# SolarSimulatorPanel.net
KiCad netlist of a schematic drawn in EAGLE
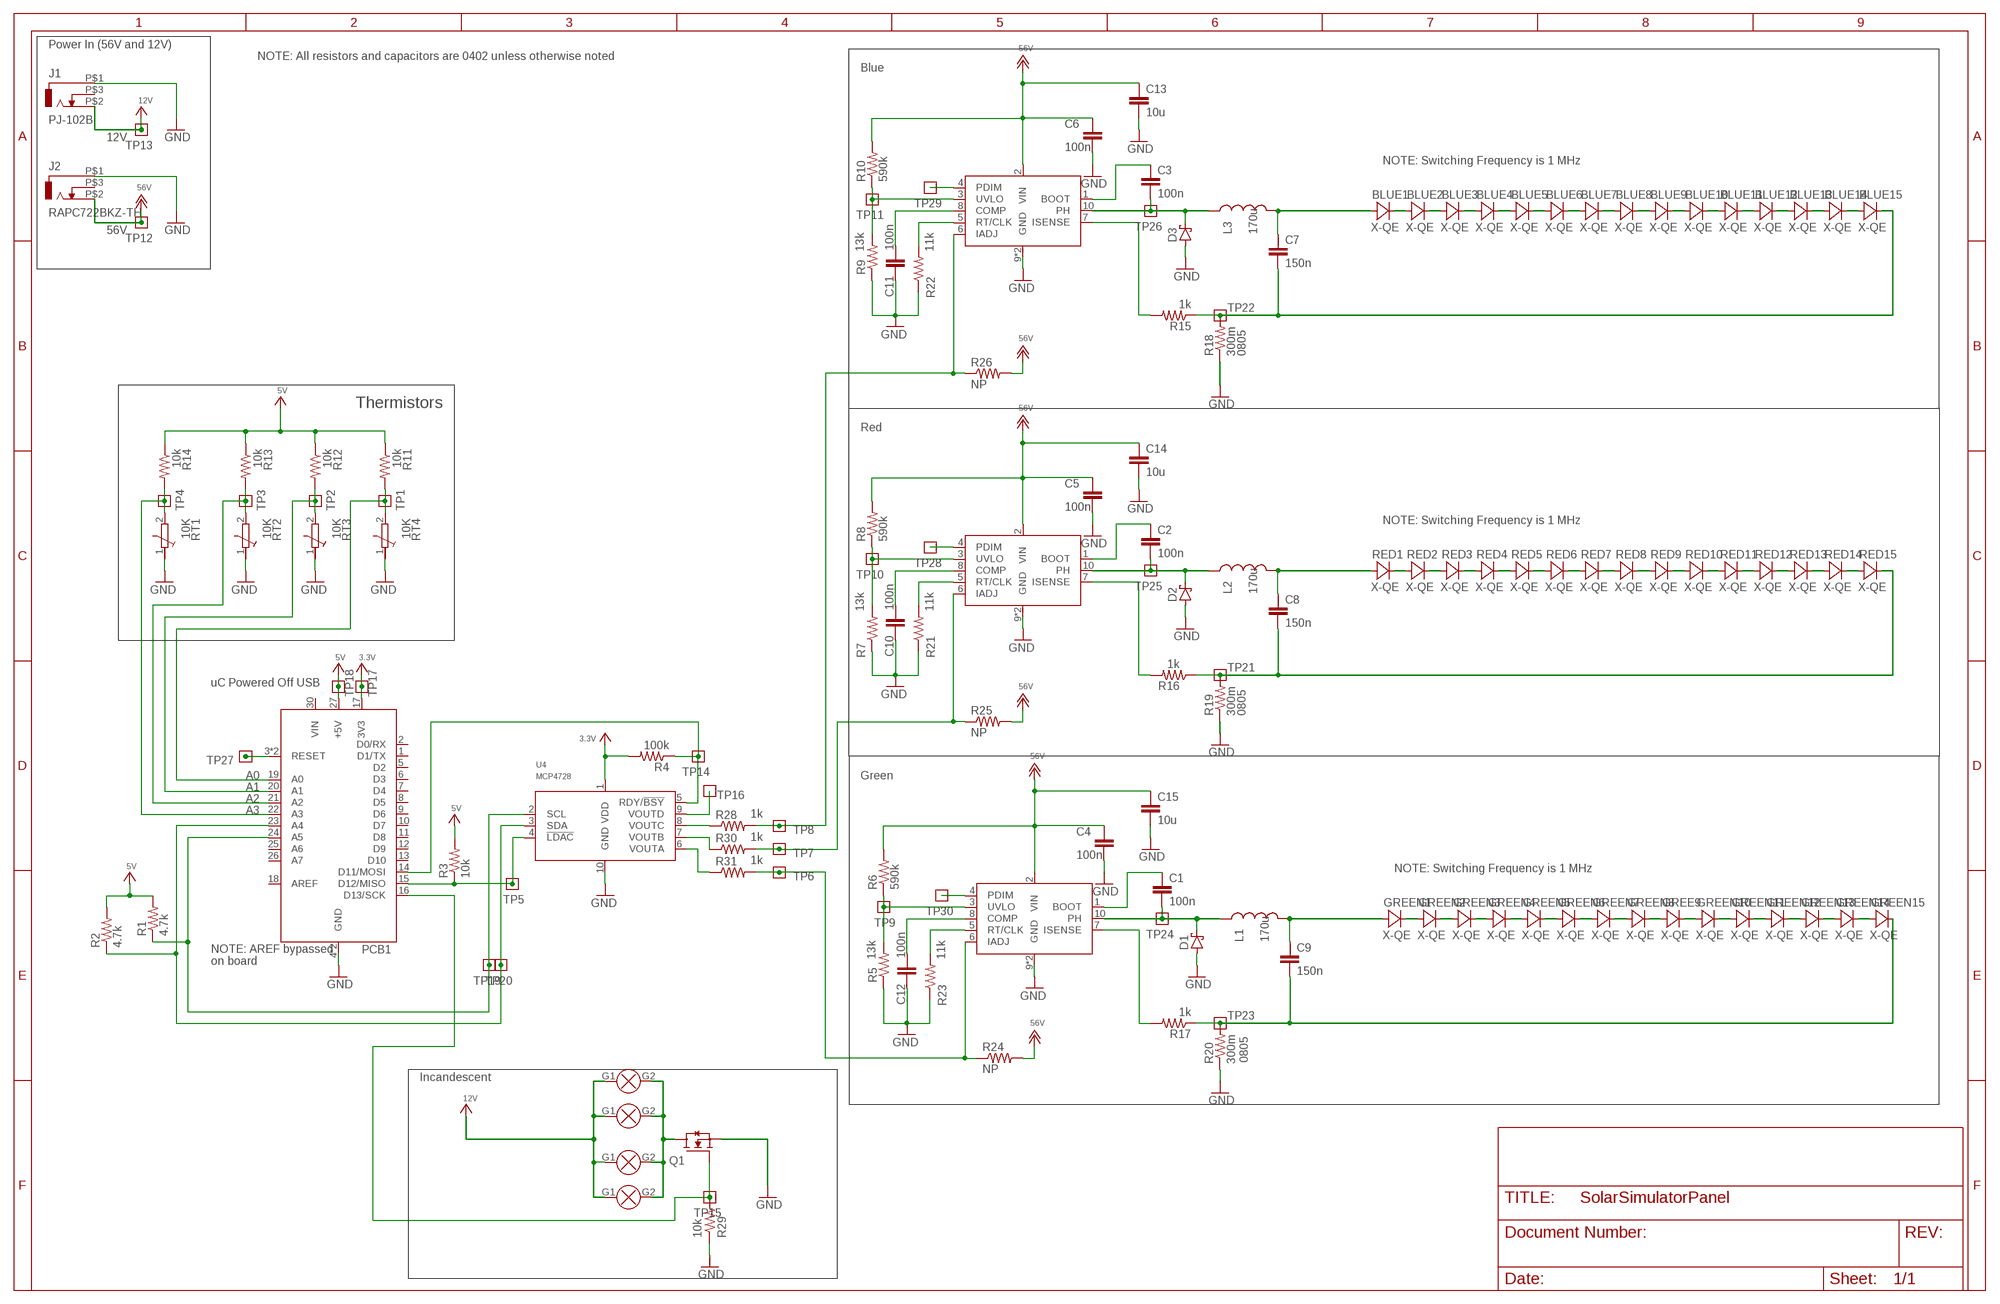
[diagram p0: schematic, sheet 1]

(export (version "E")
  (design (tool "Eeschema 10.0.6"))
  (components
    (comp (ref "BLUE1")
      (value "X-QE")
      (footprint "eagle-import:X-QE")
      (fields (field (name "MFR") "Cree") (field (name "MPN") "XQEROY-00-0000-000000L01"))
      (libsource (lib "eagle-import") (part "X-QE"))
    )
    (comp (ref "BLUE2")
      (value "X-QE")
      (footprint "eagle-import:X-QE")
      (fields (field (name "MFR") "Cree") (field (name "MPN") "XQEROY-00-0000-000000L01"))
      (libsource (lib "eagle-import") (part "X-QE"))
    )
    (comp (ref "BLUE3")
      (value "X-QE")
      (footprint "eagle-import:X-QE")
      (fields (field (name "MFR") "Cree") (field (name "MPN") "XQEROY-00-0000-000000L01"))
      (libsource (lib "eagle-import") (part "X-QE"))
    )
    (comp (ref "BLUE4")
      (value "X-QE")
      (footprint "eagle-import:X-QE")
      (fields (field (name "MFR") "Cree") (field (name "MPN") "XQEROY-00-0000-000000L01"))
      (libsource (lib "eagle-import") (part "X-QE"))
    )
    (comp (ref "BLUE5")
      (value "X-QE")
      (footprint "eagle-import:X-QE")
      (fields (field (name "MFR") "Cree") (field (name "MPN") "XQEROY-00-0000-000000L01"))
      (libsource (lib "eagle-import") (part "X-QE"))
    )
    (comp (ref "BLUE6")
      (value "X-QE")
      (footprint "eagle-import:X-QE")
      (fields (field (name "MFR") "Cree") (field (name "MPN") "XQEROY-00-0000-000000L01"))
      (libsource (lib "eagle-import") (part "X-QE"))
    )
    (comp (ref "BLUE7")
      (value "X-QE")
      (footprint "eagle-import:X-QE")
      (fields (field (name "MFR") "Cree") (field (name "MPN") "XQEROY-00-0000-000000L01"))
      (libsource (lib "eagle-import") (part "X-QE"))
    )
    (comp (ref "BLUE8")
      (value "X-QE")
      (footprint "eagle-import:X-QE")
      (fields (field (name "MFR") "Cree") (field (name "MPN") "XQEROY-00-0000-000000L01"))
      (libsource (lib "eagle-import") (part "X-QE"))
    )
    (comp (ref "BLUE9")
      (value "X-QE")
      (footprint "eagle-import:X-QE")
      (fields (field (name "MFR") "Cree") (field (name "MPN") "XQEROY-00-0000-000000L01"))
      (libsource (lib "eagle-import") (part "X-QE"))
    )
    (comp (ref "BLUE10")
      (value "X-QE")
      (footprint "eagle-import:X-QE")
      (fields (field (name "MFR") "Cree") (field (name "MPN") "XQEROY-00-0000-000000L01"))
      (libsource (lib "eagle-import") (part "X-QE"))
    )
    (comp (ref "BLUE11")
      (value "X-QE")
      (footprint "eagle-import:X-QE")
      (fields (field (name "MFR") "Cree") (field (name "MPN") "XQEROY-00-0000-000000L01"))
      (libsource (lib "eagle-import") (part "X-QE"))
    )
    (comp (ref "BLUE12")
      (value "X-QE")
      (footprint "eagle-import:X-QE")
      (fields (field (name "MFR") "Cree") (field (name "MPN") "XQEROY-00-0000-000000L01"))
      (libsource (lib "eagle-import") (part "X-QE"))
    )
    (comp (ref "BLUE13")
      (value "X-QE")
      (footprint "eagle-import:X-QE")
      (fields (field (name "MFR") "Cree") (field (name "MPN") "XQEROY-00-0000-000000L01"))
      (libsource (lib "eagle-import") (part "X-QE"))
    )
    (comp (ref "BLUE14")
      (value "X-QE")
      (footprint "eagle-import:X-QE")
      (fields (field (name "MFR") "Cree") (field (name "MPN") "XQEROY-00-0000-000000L01"))
      (libsource (lib "eagle-import") (part "X-QE"))
    )
    (comp (ref "BLUE15")
      (value "X-QE")
      (footprint "eagle-import:X-QE")
      (fields (field (name "MFR") "Cree") (field (name "MPN") "XQEROY-00-0000-000000L01"))
      (libsource (lib "eagle-import") (part "X-QE"))
    )
    (comp (ref "C1")
      (value "100n")
      (footprint "eagle-import:.0402-A-NOSILK")
      (fields (field (name "MFR") "Murata") (field (name "MPN") "GRM155R62A104KE14D"))
      (libsource (lib "eagle-import") (part "C-EU0402-A-NOSILK"))
    )
    (comp (ref "C2")
      (value "100n")
      (footprint "eagle-import:.0402-A-NOSILK")
      (fields (field (name "MFR") "Murata") (field (name "MPN") "GRM155R62A104KE14D"))
      (libsource (lib "eagle-import") (part "C-EU0402-A-NOSILK"))
    )
    (comp (ref "C3")
      (value "100n")
      (footprint "eagle-import:.0402-A-NOSILK")
      (libsource (lib "eagle-import") (part "C-EU0402-A-NOSILK"))
    )
    (comp (ref "C4")
      (value "100n")
      (footprint "eagle-import:.0402-A-NOSILK")
      (fields (field (name "MFR") "Murata") (field (name "MPN") "GRM155R62A104KE14D"))
      (libsource (lib "eagle-import") (part "C-EU0402-A-NOSILK"))
    )
    (comp (ref "C5")
      (value "100n")
      (footprint "eagle-import:.0402-A-NOSILK")
      (fields (field (name "MFR") "Murata") (field (name "MPN") "GRM155R62A104KE14D"))
      (libsource (lib "eagle-import") (part "C-EU0402-A-NOSILK"))
    )
    (comp (ref "C6")
      (value "100n")
      (footprint "eagle-import:.0402-A-NOSILK")
      (fields (field (name "MFR") "Murata") (field (name "MPN") "GRM155R62A104KE14D"))
      (libsource (lib "eagle-import") (part "C-EU0402-A-NOSILK"))
    )
    (comp (ref "C7")
      (value "150n")
      (footprint "eagle-import:C0805K")
      (fields (field (name "MFR") "Murata") (field (name "MPN") "GRM188R71H154KAC4D"))
      (libsource (lib "eagle-import") (part "rcl_334_C-EUC0805K"))
    )
    (comp (ref "C8")
      (value "150n")
      (footprint "eagle-import:C0805K")
      (fields (field (name "MFR") "Murata") (field (name "MPN") "GRM188R71H154KAC4D"))
      (libsource (lib "eagle-import") (part "rcl_334_C-EUC0805K"))
    )
    (comp (ref "C9")
      (value "150n")
      (footprint "eagle-import:C0805K")
      (fields (field (name "MFR") "Murata") (field (name "MPN") "GRM188R71H154KAC4D"))
      (libsource (lib "eagle-import") (part "rcl_334_C-EUC0805K"))
    )
    (comp (ref "C10")
      (value "100n")
      (footprint "eagle-import:.0402-A-NOSILK")
      (fields (field (name "MFR") "Murata") (field (name "MPN") "GRM155R62A104KE14D"))
      (libsource (lib "eagle-import") (part "C-EU0402-A-NOSILK"))
    )
    (comp (ref "C11")
      (value "100n")
      (footprint "eagle-import:.0402-A-NOSILK")
      (fields (field (name "MFR") "Murata") (field (name "MPN") "GRM155R62A104KE14D"))
      (libsource (lib "eagle-import") (part "C-EU0402-A-NOSILK"))
    )
    (comp (ref "C12")
      (value "100n")
      (footprint "eagle-import:.0402-A-NOSILK")
      (fields (field (name "MFR") "Murata") (field (name "MPN") "GRM155R62A104KE14D"))
      (libsource (lib "eagle-import") (part "C-EU0402-A-NOSILK"))
    )
    (comp (ref "C13")
      (value "10u")
      (footprint "eagle-import:C2220K")
      (fields (field (name "MFR") "AVX") (field (name "MPN") "22201C106MAT2A"))
      (libsource (lib "eagle-import") (part "rcl_334_C-EUC2220K"))
    )
    (comp (ref "C14")
      (value "10u")
      (footprint "eagle-import:C2220K")
      (fields (field (name "MFR") "AVX") (field (name "MPN") "22201C106MAT2A"))
      (libsource (lib "eagle-import") (part "rcl_334_C-EUC2220K"))
    )
    (comp (ref "C15")
      (value "10u")
      (footprint "eagle-import:C2220K")
      (fields (field (name "MFR") "AVX") (field (name "MPN") "22201C106MAT2A"))
      (libsource (lib "eagle-import") (part "rcl_334_C-EUC2220K"))
    )
    (comp (ref "D1")
      (value "D-MCC-SS2150")
      (footprint "eagle-import:DO-214AC")
      (fields (field (name "MFR") "Micro") (field (name "MPN") "SS2150-LTP"))
      (libsource (lib "eagle-import") (part "D-MCC-SS2150"))
    )
    (comp (ref "D2")
      (value "D-MCC-SS2150")
      (footprint "eagle-import:DO-214AC")
      (fields (field (name "MFR") "Micro") (field (name "MPN") "SS2150-LTP"))
      (libsource (lib "eagle-import") (part "D-MCC-SS2150"))
    )
    (comp (ref "D3")
      (value "D-MCC-SS2150")
      (footprint "eagle-import:DO-214AC")
      (fields (field (name "MFR") "Micro") (field (name "MPN") "SS2150-LTP"))
      (libsource (lib "eagle-import") (part "D-MCC-SS2150"))
    )
    (comp (ref "GREE9")
      (value "X-QE")
      (footprint "eagle-import:X-QE")
      (fields (field (name "MFR") "Cree") (field (name "MPN") "XQEGRN-00-0000-000000D03"))
      (libsource (lib "eagle-import") (part "X-QE"))
    )
    (comp (ref "GREEN1")
      (value "X-QE")
      (footprint "eagle-import:X-QE")
      (fields (field (name "MFR") "Cree") (field (name "MPN") "XQEGRN-00-0000-000000D03"))
      (libsource (lib "eagle-import") (part "X-QE"))
    )
    (comp (ref "GREEN2")
      (value "X-QE")
      (footprint "eagle-import:X-QE")
      (fields (field (name "MFR") "Cree") (field (name "MPN") "XQEGRN-00-0000-000000D03"))
      (libsource (lib "eagle-import") (part "X-QE"))
    )
    (comp (ref "GREEN3")
      (value "X-QE")
      (footprint "eagle-import:X-QE")
      (fields (field (name "MFR") "Cree") (field (name "MPN") "XQEGRN-00-0000-000000D03"))
      (libsource (lib "eagle-import") (part "X-QE"))
    )
    (comp (ref "GREEN4")
      (value "X-QE")
      (footprint "eagle-import:X-QE")
      (fields (field (name "MFR") "Cree") (field (name "MPN") "XQEGRN-00-0000-000000D03"))
      (libsource (lib "eagle-import") (part "X-QE"))
    )
    (comp (ref "GREEN5")
      (value "X-QE")
      (footprint "eagle-import:X-QE")
      (fields (field (name "MFR") "Cree") (field (name "MPN") "XQEGRN-00-0000-000000D03"))
      (libsource (lib "eagle-import") (part "X-QE"))
    )
    (comp (ref "GREEN6")
      (value "X-QE")
      (footprint "eagle-import:X-QE")
      (fields (field (name "MFR") "Cree") (field (name "MPN") "XQEGRN-00-0000-000000D03"))
      (libsource (lib "eagle-import") (part "X-QE"))
    )
    (comp (ref "GREEN7")
      (value "X-QE")
      (footprint "eagle-import:X-QE")
      (fields (field (name "MFR") "Cree") (field (name "MPN") "XQEGRN-00-0000-000000D03"))
      (libsource (lib "eagle-import") (part "X-QE"))
    )
    (comp (ref "GREEN8")
      (value "X-QE")
      (footprint "eagle-import:X-QE")
      (fields (field (name "MFR") "Cree") (field (name "MPN") "XQEGRN-00-0000-000000D03"))
      (libsource (lib "eagle-import") (part "X-QE"))
    )
    (comp (ref "GREEN10")
      (value "X-QE")
      (footprint "eagle-import:X-QE")
      (fields (field (name "MFR") "Cree") (field (name "MPN") "XQEGRN-00-0000-000000D03"))
      (libsource (lib "eagle-import") (part "X-QE"))
    )
    (comp (ref "GREEN11")
      (value "X-QE")
      (footprint "eagle-import:X-QE")
      (fields (field (name "MFR") "Cree") (field (name "MPN") "XQEGRN-00-0000-000000D03"))
      (libsource (lib "eagle-import") (part "X-QE"))
    )
    (comp (ref "GREEN12")
      (value "X-QE")
      (footprint "eagle-import:X-QE")
      (fields (field (name "MFR") "Cree") (field (name "MPN") "XQEGRN-00-0000-000000D03"))
      (libsource (lib "eagle-import") (part "X-QE"))
    )
    (comp (ref "GREEN13")
      (value "X-QE")
      (footprint "eagle-import:X-QE")
      (fields (field (name "MFR") "Cree") (field (name "MPN") "XQEGRN-00-0000-000000D03"))
      (libsource (lib "eagle-import") (part "X-QE"))
    )
    (comp (ref "GREEN14")
      (value "X-QE")
      (footprint "eagle-import:X-QE")
      (fields (field (name "MFR") "Cree") (field (name "MPN") "XQEGRN-00-0000-000000D03"))
      (libsource (lib "eagle-import") (part "X-QE"))
    )
    (comp (ref "GREEN15")
      (value "X-QE")
      (footprint "eagle-import:X-QE")
      (fields (field (name "MFR") "Cree") (field (name "MPN") "XQEGRN-00-0000-000000D03"))
      (libsource (lib "eagle-import") (part "X-QE"))
    )
    (comp (ref "J1")
      (value "PJ-102B")
      (footprint "eagle-import:CUI_PJ-102B")
      (fields (field (name "MF") "CUI Devices") (field (name "MFR") "Conec"))
      (libsource (lib "eagle-import") (part "PJ-102B"))
    )
    (comp (ref "J2")
      (value "RAPC722BKZ-TH")
      (footprint "eagle-import:RAPC722BKZ")
      (fields (field (name "MFR") "SwitchCraft") (field (name "MPN") "RAPC722BKZ"))
      (libsource (lib "eagle-import") (part "RAPC722BKZ-TH"))
    )
    (comp (ref "L1")
      (value "170u")
      (footprint "eagle-import:1212NONSTANDARD")
      (fields (field (name "MFR") "Amgis") (field (name "MPN") "SH150S-1.02-168"))
      (libsource (lib "eagle-import") (part "7447709681"))
    )
    (comp (ref "L2")
      (value "170u")
      (footprint "eagle-import:1212NONSTANDARD")
      (fields (field (name "MFR") "Amgis") (field (name "MPN") "SH150S-1.02-168"))
      (libsource (lib "eagle-import") (part "7447709681"))
    )
    (comp (ref "L3")
      (value "170u")
      (footprint "eagle-import:1212NONSTANDARD")
      (fields (field (name "MFR") "Amgis") (field (name "MPN") "SH150S-1.02-168"))
      (libsource (lib "eagle-import") (part "7447709681"))
    )
    (comp (ref "PCB1")
      (value "ARDUINO_NANO")
      (footprint "eagle-import:ARDUINO_NANO_SHIELD")
      (libsource (lib "eagle-import") (part "ARDUINO_NANO"))
    )
    (comp (ref "Q1")
      (value "NCH-SOT223")
      (footprint "eagle-import:SOT223")
      (fields (field (name "MFR") "Diodes") (field (name "MPN") "DMN6068SE"))
      (libsource (lib "eagle-import") (part "NCH-SOT223"))
    )
    (comp (ref "R1")
      (value "4.7k")
      (footprint "eagle-import:.0402-A-NOSILK")
      (fields (field (name "MFR") "Yageo") (field (name "MPN") "RC0402JR-074K7L"))
      (libsource (lib "eagle-import") (part "R-US_0402-A-NOSILK"))
    )
    (comp (ref "R2")
      (value "4.7k")
      (footprint "eagle-import:.0402-A-NOSILK")
      (fields (field (name "MFR") "Yageo") (field (name "MPN") "311-4.7KJRCT-ND"))
      (libsource (lib "eagle-import") (part "R-US_0402-A-NOSILK"))
    )
    (comp (ref "R3")
      (value "10k")
      (footprint "eagle-import:.0402-A-NOSILK")
      (fields (field (name "MPN") "RC0402FR-0710KL"))
      (libsource (lib "eagle-import") (part "R-US_0402-A-NOSILK"))
    )
    (comp (ref "R4")
      (value "100k")
      (footprint "eagle-import:.0402-A-NOSILK")
      (libsource (lib "eagle-import") (part "R-US_0402-A-NOSILK"))
    )
    (comp (ref "R5")
      (value "13k")
      (footprint "eagle-import:.0402-A-NOSILK")
      (fields (field (name "MFR") "Panasonic") (field (name "MPN") "ERA-2AEB133X"))
      (libsource (lib "eagle-import") (part "R-US_0402-A-NOSILK"))
    )
    (comp (ref "R6")
      (value "590k")
      (footprint "eagle-import:.0402-A-NOSILK")
      (fields (field (name "MFR") "Stackpole") (field (name "MPN") "RMCF0402FT590K"))
      (libsource (lib "eagle-import") (part "R-US_0402-A-NOSILK"))
    )
    (comp (ref "R7")
      (value "13k")
      (footprint "eagle-import:.0402-A-NOSILK")
      (fields (field (name "MFR") "Panasonic") (field (name "MPN") "ERA-2AEB133X"))
      (libsource (lib "eagle-import") (part "R-US_0402-A-NOSILK"))
    )
    (comp (ref "R8")
      (value "590k")
      (footprint "eagle-import:.0402-A-NOSILK")
      (fields (field (name "MFR") "Stackpole") (field (name "MPN") "RMCF0402FT590K"))
      (libsource (lib "eagle-import") (part "R-US_0402-A-NOSILK"))
    )
    (comp (ref "R9")
      (value "13k")
      (footprint "eagle-import:.0402-A-NOSILK")
      (fields (field (name "MFR") "Panasonic") (field (name "MPN") "ERA-2AEB133X"))
      (libsource (lib "eagle-import") (part "R-US_0402-A-NOSILK"))
    )
    (comp (ref "R10")
      (value "590k")
      (footprint "eagle-import:.0402-A-NOSILK")
      (fields (field (name "MFR") "Stackpole") (field (name "MPN") "RMCF0402FT590K"))
      (libsource (lib "eagle-import") (part "R-US_0402-A-NOSILK"))
    )
    (comp (ref "R11")
      (value "10k")
      (footprint "eagle-import:.0603-B-NOSILK")
      (fields (field (name "MPN") "RC0402FR-0710KL"))
      (libsource (lib "eagle-import") (part "R-US_0603-B-NOSILK"))
    )
    (comp (ref "R12")
      (value "10k")
      (footprint "eagle-import:.0603-B-NOSILK")
      (fields (field (name "MPN") "RC0402FR-0710KL"))
      (libsource (lib "eagle-import") (part "R-US_0603-B-NOSILK"))
    )
    (comp (ref "R13")
      (value "10k")
      (footprint "eagle-import:.0603-B-NOSILK")
      (fields (field (name "MPN") "RC0402FR-0710KL"))
      (libsource (lib "eagle-import") (part "R-US_0603-B-NOSILK"))
    )
    (comp (ref "R14")
      (value "10k")
      (footprint "eagle-import:.0603-B-NOSILK")
      (fields (field (name "MPN") "RC0402FR-0710KL"))
      (libsource (lib "eagle-import") (part "R-US_0603-B-NOSILK"))
    )
    (comp (ref "R15")
      (value "1k")
      (footprint "eagle-import:.0402-A-NOSILK")
      (fields (field (name "MFR") "Yageo") (field (name "MPN") "RC0402FR-071KL"))
      (libsource (lib "eagle-import") (part "R-US_0402-A-NOSILK"))
    )
    (comp (ref "R16")
      (value "1k")
      (footprint "eagle-import:.0402-A-NOSILK")
      (fields (field (name "MFR") "Yageo") (field (name "MPN") "RC0402FR-071KL"))
      (libsource (lib "eagle-import") (part "R-US_0402-A-NOSILK"))
    )
    (comp (ref "R17")
      (value "1k")
      (footprint "eagle-import:.0402-A-NOSILK")
      (fields (field (name "MFR") "Yageo") (field (name "MPN") "RC0402FR-071KL"))
      (libsource (lib "eagle-import") (part "R-US_0402-A-NOSILK"))
    )
    (comp (ref "R18")
      (value "300m")
      (footprint "eagle-import:R0805")
      (fields (field (name "MFR") "Panasonic") (field (name "MPN") "ERJ-6DQJR30V"))
      (libsource (lib "eagle-import") (part "rcl_334_R-US_R0805"))
    )
    (comp (ref "R19")
      (value "300m")
      (footprint "eagle-import:R0805")
      (fields (field (name "MFR") "Panasonic") (field (name "MPN") "ERJ-6DQJR30V"))
      (libsource (lib "eagle-import") (part "rcl_334_R-US_R0805"))
    )
    (comp (ref "R20")
      (value "300m")
      (footprint "eagle-import:R0805")
      (fields (field (name "MFR") "Panasonic") (field (name "MPN") "ERJ-6DQJR30V"))
      (libsource (lib "eagle-import") (part "rcl_334_R-US_R0805"))
    )
    (comp (ref "R21")
      (value "11k")
      (footprint "eagle-import:.0402-A-NOSILK")
      (fields (field (name "MFR") "Panasonic") (field (name "MPN") "ERA-3AEB113V"))
      (libsource (lib "eagle-import") (part "R-US_0402-A-NOSILK"))
    )
    (comp (ref "R22")
      (value "11k")
      (footprint "eagle-import:.0402-A-NOSILK")
      (fields (field (name "MFR") "Panasonic") (field (name "MPN") "ERA-3AEB113V"))
      (libsource (lib "eagle-import") (part "R-US_0402-A-NOSILK"))
    )
    (comp (ref "R23")
      (value "11k")
      (footprint "eagle-import:.0402-A-NOSILK")
      (fields (field (name "MFR") "Panasonic") (field (name "MPN") "ERA-3AEB113V"))
      (libsource (lib "eagle-import") (part "R-US_0402-A-NOSILK"))
    )
    (comp (ref "R24")
      (value "NP")
      (footprint "eagle-import:R0402")
      (libsource (lib "eagle-import") (part "rcl_334_R-US_R0402"))
    )
    (comp (ref "R25")
      (value "NP")
      (footprint "eagle-import:R0402")
      (libsource (lib "eagle-import") (part "rcl_334_R-US_R0402"))
    )
    (comp (ref "R26")
      (value "NP")
      (footprint "eagle-import:R0402")
      (libsource (lib "eagle-import") (part "rcl_334_R-US_R0402"))
    )
    (comp (ref "R28")
      (value "1k")
      (footprint "eagle-import:R0402")
      (fields (field (name "MFR") "Yageo") (field (name "MPN") "RC0402FR-071KL"))
      (libsource (lib "eagle-import") (part "rcl_334_R-US_R0402"))
    )
    (comp (ref "R29")
      (value "10k")
      (footprint "eagle-import:.0402-A-NOSILK")
      (fields (field (name "MPN") "RC0402FR-0710KL"))
      (libsource (lib "eagle-import") (part "R-US_0402-A-NOSILK"))
    )
    (comp (ref "R30")
      (value "1k")
      (footprint "eagle-import:R0402")
      (fields (field (name "MFR") "Yageo") (field (name "MPN") "RC0402FR-071KL"))
      (libsource (lib "eagle-import") (part "rcl_334_R-US_R0402"))
    )
    (comp (ref "R31")
      (value "1k")
      (footprint "eagle-import:R0402")
      (fields (field (name "MFR") "Yageo") (field (name "MPN") "RC0402FR-071KL"))
      (libsource (lib "eagle-import") (part "rcl_334_R-US_R0402"))
    )
    (comp (ref "RED1")
      (value "X-QE")
      (footprint "eagle-import:X-QE")
      (fields (field (name "MFR") "Cree") (field (name "MPN") "XQERED-00-0000-000000701"))
      (libsource (lib "eagle-import") (part "X-QE"))
    )
    (comp (ref "RED2")
      (value "X-QE")
      (footprint "eagle-import:X-QE")
      (fields (field (name "MFR") "Cree") (field (name "MPN") "XQERED-00-0000-000000701"))
      (libsource (lib "eagle-import") (part "X-QE"))
    )
    (comp (ref "RED3")
      (value "X-QE")
      (footprint "eagle-import:X-QE")
      (fields (field (name "MFR") "Cree") (field (name "MPN") "XQERED-00-0000-000000701"))
      (libsource (lib "eagle-import") (part "X-QE"))
    )
    (comp (ref "RED4")
      (value "X-QE")
      (footprint "eagle-import:X-QE")
      (fields (field (name "MFR") "Cree") (field (name "MPN") "XQERED-00-0000-000000701"))
      (libsource (lib "eagle-import") (part "X-QE"))
    )
    (comp (ref "RED5")
      (value "X-QE")
      (footprint "eagle-import:X-QE")
      (fields (field (name "MFR") "Cree") (field (name "MPN") "XQERED-00-0000-000000701"))
      (libsource (lib "eagle-import") (part "X-QE"))
    )
    (comp (ref "RED6")
      (value "X-QE")
      (footprint "eagle-import:X-QE")
      (fields (field (name "MFR") "Cree") (field (name "MPN") "XQERED-00-0000-000000701"))
      (libsource (lib "eagle-import") (part "X-QE"))
    )
    (comp (ref "RED7")
      (value "X-QE")
      (footprint "eagle-import:X-QE")
      (fields (field (name "MFR") "Cree") (field (name "MPN") "XQERED-00-0000-000000701"))
      (libsource (lib "eagle-import") (part "X-QE"))
    )
    (comp (ref "RED8")
      (value "X-QE")
      (footprint "eagle-import:X-QE")
      (fields (field (name "MFR") "Cree") (field (name "MPN") "XQERED-00-0000-000000701"))
      (libsource (lib "eagle-import") (part "X-QE"))
    )
    (comp (ref "RED9")
      (value "X-QE")
      (footprint "eagle-import:X-QE")
      (fields (field (name "MFR") "Cree") (field (name "MPN") "XQERED-00-0000-000000701"))
      (libsource (lib "eagle-import") (part "X-QE"))
    )
    (comp (ref "RED10")
      (value "X-QE")
      (footprint "eagle-import:X-QE")
      (fields (field (name "MFR") "Cree") (field (name "MPN") "XQERED-00-0000-000000701"))
      (libsource (lib "eagle-import") (part "X-QE"))
    )
    (comp (ref "RED11")
      (value "X-QE")
      (footprint "eagle-import:X-QE")
      (fields (field (name "MFR") "Cree") (field (name "MPN") "XQERED-00-0000-000000701"))
      (libsource (lib "eagle-import") (part "X-QE"))
    )
    (comp (ref "RED12")
      (value "X-QE")
      (footprint "eagle-import:X-QE")
      (fields (field (name "MFR") "Cree") (field (name "MPN") "XQERED-00-0000-000000701"))
      (libsource (lib "eagle-import") (part "X-QE"))
    )
    (comp (ref "RED13")
      (value "X-QE")
      (footprint "eagle-import:X-QE")
      (fields (field (name "MFR") "Cree") (field (name "MPN") "XQERED-00-0000-000000701"))
      (libsource (lib "eagle-import") (part "X-QE"))
    )
    (comp (ref "RED14")
      (value "X-QE")
      (footprint "eagle-import:X-QE")
      (fields (field (name "MFR") "Cree") (field (name "MPN") "XQERED-00-0000-000000701"))
      (libsource (lib "eagle-import") (part "X-QE"))
    )
    (comp (ref "RED15")
      (value "X-QE")
      (footprint "eagle-import:X-QE")
      (fields (field (name "MFR") "Cree") (field (name "MPN") "XQERED-00-0000-000000701"))
      (libsource (lib "eagle-import") (part "X-QE"))
    )
    (comp (ref "RT1")
      (value "10K")
      (footprint "eagle-import:R0402")
      (fields (field (name "MFR") "TDK") (field (name "MPN") "NTCG103JF103FT1"))
      (libsource (lib "eagle-import") (part "NTCTHERMISTER"))
    )
    (comp (ref "RT2")
      (value "10K")
      (footprint "eagle-import:R0402")
      (fields (field (name "MFR") "TDK") (field (name "MPN") "NTCG103JF103FT1"))
      (libsource (lib "eagle-import") (part "NTCTHERMISTER"))
    )
    (comp (ref "RT3")
      (value "10K")
      (footprint "eagle-import:R0402")
      (fields (field (name "MFR") "TDK") (field (name "MPN") "NTCG103JF103FT1"))
      (libsource (lib "eagle-import") (part "NTCTHERMISTER"))
    )
    (comp (ref "RT4")
      (value "10K")
      (footprint "eagle-import:R0402")
      (fields (field (name "MFR") "TDK") (field (name "MPN") "NTCG103JF103FT1"))
      (libsource (lib "eagle-import") (part "NTCTHERMISTER"))
    )
    (comp (ref "TP1")
      (value "TEST-POINT")
      (footprint "eagle-import:2MM-TEST-POINT")
      (libsource (lib "eagle-import") (part "TEST-POINT"))
    )
    (comp (ref "TP2")
      (value "TEST-POINT")
      (footprint "eagle-import:2MM-TEST-POINT")
      (libsource (lib "eagle-import") (part "TEST-POINT"))
    )
    (comp (ref "TP3")
      (value "TEST-POINT")
      (footprint "eagle-import:2MM-TEST-POINT")
      (libsource (lib "eagle-import") (part "TEST-POINT"))
    )
    (comp (ref "TP4")
      (value "TEST-POINT")
      (footprint "eagle-import:2MM-TEST-POINT")
      (libsource (lib "eagle-import") (part "TEST-POINT"))
    )
    (comp (ref "TP5")
      (value "TEST-POINT")
      (footprint "eagle-import:2MM-TEST-POINT")
      (libsource (lib "eagle-import") (part "TEST-POINT"))
    )
    (comp (ref "TP6")
      (value "TEST-POINT")
      (footprint "eagle-import:2MM-TEST-POINT")
      (libsource (lib "eagle-import") (part "TEST-POINT"))
    )
    (comp (ref "TP7")
      (value "TEST-POINT")
      (footprint "eagle-import:2MM-TEST-POINT")
      (libsource (lib "eagle-import") (part "TEST-POINT"))
    )
    (comp (ref "TP8")
      (value "TEST-POINT")
      (footprint "eagle-import:2MM-TEST-POINT")
      (libsource (lib "eagle-import") (part "TEST-POINT"))
    )
    (comp (ref "TP9")
      (value "TEST-POINT")
      (footprint "eagle-import:2MM-TEST-POINT")
      (libsource (lib "eagle-import") (part "TEST-POINT"))
    )
    (comp (ref "TP10")
      (value "TEST-POINT")
      (footprint "eagle-import:2MM-TEST-POINT")
      (libsource (lib "eagle-import") (part "TEST-POINT"))
    )
    (comp (ref "TP11")
      (value "TEST-POINT")
      (footprint "eagle-import:2MM-TEST-POINT")
      (libsource (lib "eagle-import") (part "TEST-POINT"))
    )
    (comp (ref "TP12")
      (value "TEST-POINT")
      (footprint "eagle-import:2MM-TEST-POINT")
      (libsource (lib "eagle-import") (part "TEST-POINT"))
    )
    (comp (ref "TP13")
      (value "TEST-POINT")
      (footprint "eagle-import:2MM-TEST-POINT")
      (libsource (lib "eagle-import") (part "TEST-POINT"))
    )
    (comp (ref "TP14")
      (value "TEST-POINT")
      (footprint "eagle-import:2MM-TEST-POINT")
      (libsource (lib "eagle-import") (part "TEST-POINT"))
    )
    (comp (ref "TP15")
      (value "TEST-POINT")
      (footprint "eagle-import:2MM-TEST-POINT")
      (libsource (lib "eagle-import") (part "TEST-POINT"))
    )
    (comp (ref "TP16")
      (value "TEST-POINT")
      (footprint "eagle-import:2MM-TEST-POINT")
      (libsource (lib "eagle-import") (part "TEST-POINT"))
    )
    (comp (ref "TP17")
      (value "TEST-POINT")
      (footprint "eagle-import:2MM-TEST-POINT")
      (libsource (lib "eagle-import") (part "TEST-POINT"))
    )
    (comp (ref "TP18")
      (value "TEST-POINT")
      (footprint "eagle-import:2MM-TEST-POINT")
      (libsource (lib "eagle-import") (part "TEST-POINT"))
    )
    (comp (ref "TP19")
      (value "TEST-POINT")
      (footprint "eagle-import:2MM-TEST-POINT")
      (libsource (lib "eagle-import") (part "TEST-POINT"))
    )
    (comp (ref "TP20")
      (value "TEST-POINT")
      (footprint "eagle-import:2MM-TEST-POINT")
      (libsource (lib "eagle-import") (part "TEST-POINT"))
    )
    (comp (ref "TP21")
      (value "TEST-POINT")
      (footprint "eagle-import:2MM-TEST-POINT")
      (libsource (lib "eagle-import") (part "TEST-POINT"))
    )
    (comp (ref "TP22")
      (value "TEST-POINT")
      (footprint "eagle-import:2MM-TEST-POINT")
      (libsource (lib "eagle-import") (part "TEST-POINT"))
    )
    (comp (ref "TP23")
      (value "TEST-POINT")
      (footprint "eagle-import:2MM-TEST-POINT")
      (libsource (lib "eagle-import") (part "TEST-POINT"))
    )
    (comp (ref "TP24")
      (value "TEST-POINT")
      (footprint "eagle-import:2MM-TEST-POINT")
      (libsource (lib "eagle-import") (part "TEST-POINT"))
    )
    (comp (ref "TP25")
      (value "TEST-POINT")
      (footprint "eagle-import:2MM-TEST-POINT")
      (libsource (lib "eagle-import") (part "TEST-POINT"))
    )
    (comp (ref "TP26")
      (value "TEST-POINT")
      (footprint "eagle-import:2MM-TEST-POINT")
      (libsource (lib "eagle-import") (part "TEST-POINT"))
    )
    (comp (ref "TP27")
      (value "TEST-POINT")
      (footprint "eagle-import:2MM-TEST-POINT")
      (libsource (lib "eagle-import") (part "TEST-POINT"))
    )
    (comp (ref "TP28")
      (value "TEST-POINT")
      (footprint "eagle-import:2MM-TEST-POINT")
      (libsource (lib "eagle-import") (part "TEST-POINT"))
    )
    (comp (ref "TP29")
      (value "TEST-POINT")
      (footprint "eagle-import:2MM-TEST-POINT")
      (libsource (lib "eagle-import") (part "TEST-POINT"))
    )
    (comp (ref "TP30")
      (value "TEST-POINT")
      (footprint "eagle-import:2MM-TEST-POINT")
      (libsource (lib "eagle-import") (part "TEST-POINT"))
    )
    (comp (ref "U$7")
      (value "HL_G4BULB")
      (footprint "eagle-import:G4BASE")
      (fields (field (name "MFR") "Plusrite") (field (name "MPN") "3301"))
      (libsource (lib "eagle-import") (part "HL_G4BULB"))
    )
    (comp (ref "U$8")
      (value "HL_G4BULB")
      (footprint "eagle-import:G4BASE")
      (fields (field (name "MPN") "3301"))
      (libsource (lib "eagle-import") (part "HL_G4BULB"))
    )
    (comp (ref "U$9")
      (value "HL_G4BULB")
      (footprint "eagle-import:G4BASE")
      (fields (field (name "MFR") "Plusrite") (field (name "MPN") "3301"))
      (libsource (lib "eagle-import") (part "HL_G4BULB"))
    )
    (comp (ref "U$10")
      (value "HL_G4BULB")
      (footprint "eagle-import:G4BASE")
      (fields (field (name "MFR") "Plusrite") (field (name "MPN") "3301"))
      (libsource (lib "eagle-import") (part "HL_G4BULB"))
    )
    (comp (ref "U1")
      (value "tps92512")
      (footprint "eagle-import:MSOP10")
      (fields (field (name "MFR") "Texas Instruments") (field (name "MPN") "TPS92512DGQR"))
      (libsource (lib "eagle-import") (part "TPS92512"))
    )
    (comp (ref "U2")
      (value "tps92512")
      (footprint "eagle-import:MSOP10")
      (fields (field (name "MFR") "Texas Instruments") (field (name "MPN") "TPS92512DGQR"))
      (libsource (lib "eagle-import") (part "TPS92512"))
    )
    (comp (ref "U3")
      (value "tps92512")
      (footprint "eagle-import:MSOP10")
      (fields (field (name "MFR") "Texas Instruments") (field (name "MPN") "TPS92512DGQR"))
      (libsource (lib "eagle-import") (part "TPS92512"))
    )
    (comp (ref "U4")
      (value "MCP4728")
      (footprint "eagle-import:MSOP10")
      (fields (field (name "MFR") "Microchip") (field (name "MPN") "MCP4728T-E/UN"))
      (libsource (lib "eagle-import") (part "MCP4728"))
    )
  )
  (nets
    (net (code "1") (name "/A0") (class "Default")
      (node (ref "PCB1") (pin "19") (pinfunction "A0_19") (pintype "input"))
      (node (ref "R11") (pin "2") (pinfunction "2_2") (pintype "passive"))
      (node (ref "RT4") (pin "2") (pinfunction "E_2") (pintype "passive"))
      (node (ref "TP1") (pin "1") (pinfunction "1_1") (pintype "passive"))
    )
    (net (code "2") (name "/A1") (class "Default")
      (node (ref "PCB1") (pin "20") (pinfunction "A1_20") (pintype "input"))
      (node (ref "R12") (pin "2") (pinfunction "2_2") (pintype "passive"))
      (node (ref "RT3") (pin "2") (pinfunction "E_2") (pintype "passive"))
      (node (ref "TP2") (pin "1") (pinfunction "1_1") (pintype "passive"))
    )
    (net (code "3") (name "/A2") (class "Default")
      (node (ref "PCB1") (pin "21") (pinfunction "A2_21") (pintype "input"))
      (node (ref "R13") (pin "2") (pinfunction "2_2") (pintype "passive"))
      (node (ref "RT2") (pin "2") (pinfunction "E_2") (pintype "passive"))
      (node (ref "TP3") (pin "1") (pinfunction "1_1") (pintype "passive"))
    )
    (net (code "4") (name "/A3") (class "Default")
      (node (ref "PCB1") (pin "22") (pinfunction "A3_22") (pintype "input"))
      (node (ref "R14") (pin "2") (pinfunction "2_2") (pintype "passive"))
      (node (ref "RT1") (pin "2") (pinfunction "E_2") (pintype "passive"))
      (node (ref "TP4") (pin "1") (pinfunction "1_1") (pintype "passive"))
    )
    (net (code "5") (name "/AREF") (class "Default")
      (node (ref "PCB1") (pin "18") (pinfunction "AREF_18") (pintype "power_in"))
    )
    (net (code "6") (name "/VIN") (class "Default")
      (node (ref "PCB1") (pin "30") (pinfunction "VIN_30") (pintype "power_in"))
    )
    (net (code "7") (name "3.3V") (class "Default")
      (node (ref "PCB1") (pin "17") (pinfunction "3V3_17") (pintype "power_in"))
      (node (ref "R4") (pin "2") (pinfunction "2_2") (pintype "passive"))
      (node (ref "TP17") (pin "1") (pinfunction "1_1") (pintype "passive"))
      (node (ref "U4") (pin "1") (pinfunction "VDD_1") (pintype "bidirectional"))
    )
    (net (code "8") (name "5V") (class "Default")
      (node (ref "PCB1") (pin "27") (pinfunction "+5V_27") (pintype "power_in"))
      (node (ref "R1") (pin "2") (pinfunction "2_2") (pintype "passive"))
      (node (ref "R11") (pin "1") (pinfunction "1_1") (pintype "passive"))
      (node (ref "R12") (pin "1") (pinfunction "1_1") (pintype "passive"))
      (node (ref "R13") (pin "1") (pinfunction "1_1") (pintype "passive"))
      (node (ref "R14") (pin "1") (pinfunction "1_1") (pintype "passive"))
      (node (ref "R2") (pin "2") (pinfunction "2_2") (pintype "passive"))
      (node (ref "R3") (pin "2") (pinfunction "2_2") (pintype "passive"))
      (node (ref "TP18") (pin "1") (pinfunction "1_1") (pintype "passive"))
    )
    (net (code "9") (name "12V") (class "Default")
      (node (ref "J1") (pin "P$2") (pinfunction "3_P$2") (pintype "passive"))
      (node (ref "TP13") (pin "1") (pinfunction "1_1") (pintype "passive"))
      (node (ref "U$10") (pin "G1") (pinfunction "P$1_G1") (pintype "bidirectional"))
      (node (ref "U$7") (pin "G1") (pinfunction "P$1_G1") (pintype "bidirectional"))
      (node (ref "U$8") (pin "G1") (pinfunction "P$1_G1") (pintype "bidirectional"))
      (node (ref "U$9") (pin "G1") (pinfunction "P$1_G1") (pintype "bidirectional"))
    )
    (net (code "10") (name "56V") (class "Default")
      (node (ref "C13") (pin "1") (pinfunction "1_1") (pintype "passive"))
      (node (ref "C14") (pin "1") (pinfunction "1_1") (pintype "passive"))
      (node (ref "C15") (pin "1") (pinfunction "1_1") (pintype "passive"))
      (node (ref "C4") (pin "1") (pinfunction "1_1") (pintype "passive"))
      (node (ref "C5") (pin "1") (pinfunction "1_1") (pintype "passive"))
      (node (ref "C6") (pin "1") (pinfunction "1_1") (pintype "passive"))
      (node (ref "J2") (pin "P$2") (pinfunction "3_P$2") (pintype "passive"))
      (node (ref "R10") (pin "2") (pinfunction "2_2") (pintype "passive"))
      (node (ref "R24") (pin "2") (pinfunction "2_2") (pintype "passive"))
      (node (ref "R25") (pin "2") (pinfunction "2_2") (pintype "passive"))
      (node (ref "R26") (pin "2") (pinfunction "2_2") (pintype "passive"))
      (node (ref "R6") (pin "2") (pinfunction "2_2") (pintype "passive"))
      (node (ref "R8") (pin "2") (pinfunction "2_2") (pintype "passive"))
      (node (ref "TP12") (pin "1") (pinfunction "1_1") (pintype "passive"))
      (node (ref "U1") (pin "2") (pinfunction "VIN_2") (pintype "bidirectional"))
      (node (ref "U2") (pin "2") (pinfunction "VIN_2") (pintype "bidirectional"))
      (node (ref "U3") (pin "2") (pinfunction "VIN_2") (pintype "bidirectional"))
    )
    (net (code "11") (name "GND") (class "Default")
      (node (ref "C10") (pin "2") (pinfunction "2_2") (pintype "passive"))
      (node (ref "C11") (pin "2") (pinfunction "2_2") (pintype "passive"))
      (node (ref "C12") (pin "2") (pinfunction "2_2") (pintype "passive"))
      (node (ref "C13") (pin "2") (pinfunction "2_2") (pintype "passive"))
      (node (ref "C14") (pin "2") (pinfunction "2_2") (pintype "passive"))
      (node (ref "C15") (pin "2") (pinfunction "2_2") (pintype "passive"))
      (node (ref "C4") (pin "2") (pinfunction "2_2") (pintype "passive"))
      (node (ref "C5") (pin "2") (pinfunction "2_2") (pintype "passive"))
      (node (ref "C6") (pin "2") (pinfunction "2_2") (pintype "passive"))
      (node (ref "D1") (pin "A") (pinfunction "A_A") (pintype "passive"))
      (node (ref "D2") (pin "A") (pinfunction "A_A") (pintype "passive"))
      (node (ref "D3") (pin "A") (pinfunction "A_A") (pintype "passive"))
      (node (ref "J1") (pin "P$1") (pinfunction "1_P$1") (pintype "passive"))
      (node (ref "J2") (pin "P$1") (pinfunction "1_P$1") (pintype "passive"))
      (node (ref "PCB1") (pin "29") (pinfunction "GND_29") (pintype "power_in"))
      (node (ref "PCB1") (pin "4") (pinfunction "GND_4") (pintype "power_in"))
      (node (ref "Q1") (pin "3") (pinfunction "S_3") (pintype "passive"))
      (node (ref "R18") (pin "1") (pinfunction "1_1") (pintype "passive"))
      (node (ref "R19") (pin "1") (pinfunction "1_1") (pintype "passive"))
      (node (ref "R20") (pin "1") (pinfunction "1_1") (pintype "passive"))
      (node (ref "R21") (pin "1") (pinfunction "1_1") (pintype "passive"))
      (node (ref "R22") (pin "1") (pinfunction "1_1") (pintype "passive"))
      (node (ref "R23") (pin "1") (pinfunction "1_1") (pintype "passive"))
      (node (ref "R29") (pin "1") (pinfunction "1_1") (pintype "passive"))
      (node (ref "R5") (pin "1") (pinfunction "1_1") (pintype "passive"))
      (node (ref "R7") (pin "1") (pinfunction "1_1") (pintype "passive"))
      (node (ref "R9") (pin "1") (pinfunction "1_1") (pintype "passive"))
      (node (ref "RT1") (pin "1") (pinfunction "A_1") (pintype "passive"))
      (node (ref "RT2") (pin "1") (pinfunction "A_1") (pintype "passive"))
      (node (ref "RT3") (pin "1") (pinfunction "A_1") (pintype "passive"))
      (node (ref "RT4") (pin "1") (pinfunction "A_1") (pintype "passive"))
      (node (ref "U1") (pin "9") (pinfunction "GND_9") (pintype "bidirectional"))
      (node (ref "U1") (pin "GND") (pinfunction "GND_GND") (pintype "bidirectional"))
      (node (ref "U2") (pin "9") (pinfunction "GND_9") (pintype "bidirectional"))
      (node (ref "U2") (pin "GND") (pinfunction "GND_GND") (pintype "bidirectional"))
      (node (ref "U3") (pin "9") (pinfunction "GND_9") (pintype "bidirectional"))
      (node (ref "U3") (pin "GND") (pinfunction "GND_GND") (pintype "bidirectional"))
      (node (ref "U4") (pin "10") (pinfunction "GND_10") (pintype "bidirectional"))
    )
    (net (code "12") (name "Net-(BLUE1-A)") (class "Default")
      (node (ref "BLUE1") (pin "ANODE") (pinfunction "A_ANODE") (pintype "passive"))
      (node (ref "C7") (pin "1") (pinfunction "1_1") (pintype "passive"))
      (node (ref "L3") (pin "P$2") (pinfunction "2_P$2") (pintype "passive"))
    )
    (net (code "13") (name "Net-(BLUE1-C)") (class "Default")
      (node (ref "BLUE1") (pin "CATHODE") (pinfunction "C_CATHODE") (pintype "passive"))
      (node (ref "BLUE2") (pin "ANODE") (pinfunction "A_ANODE") (pintype "passive"))
    )
    (net (code "14") (name "Net-(BLUE2-C)") (class "Default")
      (node (ref "BLUE2") (pin "CATHODE") (pinfunction "C_CATHODE") (pintype "passive"))
      (node (ref "BLUE3") (pin "ANODE") (pinfunction "A_ANODE") (pintype "passive"))
    )
    (net (code "15") (name "Net-(BLUE3-C)") (class "Default")
      (node (ref "BLUE3") (pin "CATHODE") (pinfunction "C_CATHODE") (pintype "passive"))
      (node (ref "BLUE4") (pin "ANODE") (pinfunction "A_ANODE") (pintype "passive"))
    )
    (net (code "16") (name "Net-(BLUE4-C)") (class "Default")
      (node (ref "BLUE4") (pin "CATHODE") (pinfunction "C_CATHODE") (pintype "passive"))
      (node (ref "BLUE5") (pin "ANODE") (pinfunction "A_ANODE") (pintype "passive"))
    )
    (net (code "17") (name "Net-(BLUE5-C)") (class "Default")
      (node (ref "BLUE5") (pin "CATHODE") (pinfunction "C_CATHODE") (pintype "passive"))
      (node (ref "BLUE6") (pin "ANODE") (pinfunction "A_ANODE") (pintype "passive"))
    )
    (net (code "18") (name "Net-(BLUE6-C)") (class "Default")
      (node (ref "BLUE6") (pin "CATHODE") (pinfunction "C_CATHODE") (pintype "passive"))
      (node (ref "BLUE7") (pin "ANODE") (pinfunction "A_ANODE") (pintype "passive"))
    )
    (net (code "19") (name "Net-(BLUE7-C)") (class "Default")
      (node (ref "BLUE7") (pin "CATHODE") (pinfunction "C_CATHODE") (pintype "passive"))
      (node (ref "BLUE8") (pin "ANODE") (pinfunction "A_ANODE") (pintype "passive"))
    )
    (net (code "20") (name "Net-(BLUE8-C)") (class "Default")
      (node (ref "BLUE8") (pin "CATHODE") (pinfunction "C_CATHODE") (pintype "passive"))
      (node (ref "BLUE9") (pin "ANODE") (pinfunction "A_ANODE") (pintype "passive"))
    )
    (net (code "21") (name "Net-(BLUE10-A)") (class "Default")
      (node (ref "BLUE10") (pin "ANODE") (pinfunction "A_ANODE") (pintype "passive"))
      (node (ref "BLUE9") (pin "CATHODE") (pinfunction "C_CATHODE") (pintype "passive"))
    )
    (net (code "22") (name "Net-(BLUE10-C)") (class "Default")
      (node (ref "BLUE10") (pin "CATHODE") (pinfunction "C_CATHODE") (pintype "passive"))
      (node (ref "BLUE11") (pin "ANODE") (pinfunction "A_ANODE") (pintype "passive"))
    )
    (net (code "23") (name "Net-(BLUE11-C)") (class "Default")
      (node (ref "BLUE11") (pin "CATHODE") (pinfunction "C_CATHODE") (pintype "passive"))
      (node (ref "BLUE12") (pin "ANODE") (pinfunction "A_ANODE") (pintype "passive"))
    )
    (net (code "24") (name "Net-(BLUE12-C)") (class "Default")
      (node (ref "BLUE12") (pin "CATHODE") (pinfunction "C_CATHODE") (pintype "passive"))
      (node (ref "BLUE13") (pin "ANODE") (pinfunction "A_ANODE") (pintype "passive"))
    )
    (net (code "25") (name "Net-(BLUE13-C)") (class "Default")
      (node (ref "BLUE13") (pin "CATHODE") (pinfunction "C_CATHODE") (pintype "passive"))
      (node (ref "BLUE14") (pin "ANODE") (pinfunction "A_ANODE") (pintype "passive"))
    )
    (net (code "26") (name "Net-(BLUE14-C)") (class "Default")
      (node (ref "BLUE14") (pin "CATHODE") (pinfunction "C_CATHODE") (pintype "passive"))
      (node (ref "BLUE15") (pin "ANODE") (pinfunction "A_ANODE") (pintype "passive"))
    )
    (net (code "27") (name "Net-(BLUE15-C)") (class "Default")
      (node (ref "BLUE15") (pin "CATHODE") (pinfunction "C_CATHODE") (pintype "passive"))
      (node (ref "C7") (pin "2") (pinfunction "2_2") (pintype "passive"))
      (node (ref "R15") (pin "1") (pinfunction "1_1") (pintype "passive"))
      (node (ref "R18") (pin "2") (pinfunction "2_2") (pintype "passive"))
      (node (ref "TP22") (pin "1") (pinfunction "1_1") (pintype "passive"))
    )
    (net (code "28") (name "Net-(GREE9-A)") (class "Default")
      (node (ref "GREE9") (pin "ANODE") (pinfunction "A_ANODE") (pintype "passive"))
      (node (ref "GREEN8") (pin "CATHODE") (pinfunction "C_CATHODE") (pintype "passive"))
    )
    (net (code "29") (name "Net-(GREE9-C)") (class "Default")
      (node (ref "GREE9") (pin "CATHODE") (pinfunction "C_CATHODE") (pintype "passive"))
      (node (ref "GREEN10") (pin "ANODE") (pinfunction "A_ANODE") (pintype "passive"))
    )
    (net (code "30") (name "Net-(GREEN1-A)") (class "Default")
      (node (ref "C9") (pin "1") (pinfunction "1_1") (pintype "passive"))
      (node (ref "GREEN1") (pin "ANODE") (pinfunction "A_ANODE") (pintype "passive"))
      (node (ref "L1") (pin "P$2") (pinfunction "2_P$2") (pintype "passive"))
    )
    (net (code "31") (name "Net-(GREEN1-C)") (class "Default")
      (node (ref "GREEN1") (pin "CATHODE") (pinfunction "C_CATHODE") (pintype "passive"))
      (node (ref "GREEN2") (pin "ANODE") (pinfunction "A_ANODE") (pintype "passive"))
    )
    (net (code "32") (name "Net-(GREEN2-C)") (class "Default")
      (node (ref "GREEN2") (pin "CATHODE") (pinfunction "C_CATHODE") (pintype "passive"))
      (node (ref "GREEN3") (pin "ANODE") (pinfunction "A_ANODE") (pintype "passive"))
    )
    (net (code "33") (name "Net-(GREEN3-C)") (class "Default")
      (node (ref "GREEN3") (pin "CATHODE") (pinfunction "C_CATHODE") (pintype "passive"))
      (node (ref "GREEN4") (pin "ANODE") (pinfunction "A_ANODE") (pintype "passive"))
    )
    (net (code "34") (name "Net-(GREEN4-C)") (class "Default")
      (node (ref "GREEN4") (pin "CATHODE") (pinfunction "C_CATHODE") (pintype "passive"))
      (node (ref "GREEN5") (pin "ANODE") (pinfunction "A_ANODE") (pintype "passive"))
    )
    (net (code "35") (name "Net-(GREEN5-C)") (class "Default")
      (node (ref "GREEN5") (pin "CATHODE") (pinfunction "C_CATHODE") (pintype "passive"))
      (node (ref "GREEN6") (pin "ANODE") (pinfunction "A_ANODE") (pintype "passive"))
    )
    (net (code "36") (name "Net-(GREEN6-C)") (class "Default")
      (node (ref "GREEN6") (pin "CATHODE") (pinfunction "C_CATHODE") (pintype "passive"))
      (node (ref "GREEN7") (pin "ANODE") (pinfunction "A_ANODE") (pintype "passive"))
    )
    (net (code "37") (name "Net-(GREEN7-C)") (class "Default")
      (node (ref "GREEN7") (pin "CATHODE") (pinfunction "C_CATHODE") (pintype "passive"))
      (node (ref "GREEN8") (pin "ANODE") (pinfunction "A_ANODE") (pintype "passive"))
    )
    (net (code "38") (name "Net-(GREEN10-C)") (class "Default")
      (node (ref "GREEN10") (pin "CATHODE") (pinfunction "C_CATHODE") (pintype "passive"))
      (node (ref "GREEN11") (pin "ANODE") (pinfunction "A_ANODE") (pintype "passive"))
    )
    (net (code "39") (name "Net-(GREEN11-C)") (class "Default")
      (node (ref "GREEN11") (pin "CATHODE") (pinfunction "C_CATHODE") (pintype "passive"))
      (node (ref "GREEN12") (pin "ANODE") (pinfunction "A_ANODE") (pintype "passive"))
    )
    (net (code "40") (name "Net-(GREEN12-C)") (class "Default")
      (node (ref "GREEN12") (pin "CATHODE") (pinfunction "C_CATHODE") (pintype "passive"))
      (node (ref "GREEN13") (pin "ANODE") (pinfunction "A_ANODE") (pintype "passive"))
    )
    (net (code "41") (name "Net-(GREEN13-C)") (class "Default")
      (node (ref "GREEN13") (pin "CATHODE") (pinfunction "C_CATHODE") (pintype "passive"))
      (node (ref "GREEN14") (pin "ANODE") (pinfunction "A_ANODE") (pintype "passive"))
    )
    (net (code "42") (name "Net-(GREEN14-C)") (class "Default")
      (node (ref "GREEN14") (pin "CATHODE") (pinfunction "C_CATHODE") (pintype "passive"))
      (node (ref "GREEN15") (pin "ANODE") (pinfunction "A_ANODE") (pintype "passive"))
    )
    (net (code "43") (name "Net-(GREEN15-C)") (class "Default")
      (node (ref "C9") (pin "2") (pinfunction "2_2") (pintype "passive"))
      (node (ref "GREEN15") (pin "CATHODE") (pinfunction "C_CATHODE") (pintype "passive"))
      (node (ref "R17") (pin "1") (pinfunction "1_1") (pintype "passive"))
      (node (ref "R20") (pin "2") (pinfunction "2_2") (pintype "passive"))
      (node (ref "TP23") (pin "1") (pinfunction "1_1") (pintype "passive"))
    )
    (net (code "44") (name "Net-(L1-1)") (class "Default")
      (node (ref "C1") (pin "2") (pinfunction "2_2") (pintype "passive"))
      (node (ref "D1") (pin "C") (pinfunction "C_C") (pintype "passive"))
      (node (ref "L1") (pin "P$1") (pinfunction "1_P$1") (pintype "passive"))
      (node (ref "TP24") (pin "1") (pinfunction "1_1") (pintype "passive"))
      (node (ref "U3") (pin "10") (pinfunction "PH_10") (pintype "bidirectional"))
    )
    (net (code "45") (name "Net-(L2-1)") (class "Default")
      (node (ref "C2") (pin "2") (pinfunction "2_2") (pintype "passive"))
      (node (ref "D2") (pin "C") (pinfunction "C_C") (pintype "passive"))
      (node (ref "L2") (pin "P$1") (pinfunction "1_P$1") (pintype "passive"))
      (node (ref "TP25") (pin "1") (pinfunction "1_1") (pintype "passive"))
      (node (ref "U2") (pin "10") (pinfunction "PH_10") (pintype "bidirectional"))
    )
    (net (code "46") (name "Net-(L2-2)") (class "Default")
      (node (ref "C8") (pin "1") (pinfunction "1_1") (pintype "passive"))
      (node (ref "L2") (pin "P$2") (pinfunction "2_P$2") (pintype "passive"))
      (node (ref "RED1") (pin "ANODE") (pinfunction "A_ANODE") (pintype "passive"))
    )
    (net (code "47") (name "Net-(L3-1)") (class "Default")
      (node (ref "C3") (pin "2") (pinfunction "2_2") (pintype "passive"))
      (node (ref "D3") (pin "C") (pinfunction "C_C") (pintype "passive"))
      (node (ref "L3") (pin "P$1") (pinfunction "1_P$1") (pintype "passive"))
      (node (ref "TP26") (pin "1") (pinfunction "1_1") (pintype "passive"))
      (node (ref "U1") (pin "10") (pinfunction "PH_10") (pintype "bidirectional"))
    )
    (net (code "48") (name "Net-(PCB1-A4)") (class "Default")
      (node (ref "PCB1") (pin "23") (pinfunction "A4_23") (pintype "input"))
      (node (ref "R2") (pin "1") (pinfunction "1_1") (pintype "passive"))
      (node (ref "TP20") (pin "1") (pinfunction "1_1") (pintype "passive"))
      (node (ref "U4") (pin "3") (pinfunction "SDA_3") (pintype "bidirectional"))
    )
    (net (code "49") (name "Net-(PCB1-A5)") (class "Default")
      (node (ref "PCB1") (pin "24") (pinfunction "A5_24") (pintype "input"))
      (node (ref "R1") (pin "1") (pinfunction "1_1") (pintype "passive"))
      (node (ref "TP19") (pin "1") (pinfunction "1_1") (pintype "passive"))
      (node (ref "U4") (pin "2") (pinfunction "SCL_2") (pintype "bidirectional"))
    )
    (net (code "50") (name "Net-(PCB1-D11{slash}MOSI)") (class "Default")
      (node (ref "PCB1") (pin "14") (pinfunction "D11/MOSI_14") (pintype "bidirectional"))
      (node (ref "R4") (pin "1") (pinfunction "1_1") (pintype "passive"))
      (node (ref "TP14") (pin "1") (pinfunction "1_1") (pintype "passive"))
      (node (ref "U4") (pin "5") (pinfunction "RDY/~{BSY}_5") (pintype "bidirectional"))
    )
    (net (code "51") (name "Net-(PCB1-D12{slash}MISO)") (class "Default")
      (node (ref "PCB1") (pin "15") (pinfunction "D12/MISO_15") (pintype "bidirectional"))
      (node (ref "R3") (pin "1") (pinfunction "1_1") (pintype "passive"))
      (node (ref "TP5") (pin "1") (pinfunction "1_1") (pintype "passive"))
      (node (ref "U4") (pin "4") (pinfunction "~{LDAC}_4") (pintype "bidirectional"))
    )
    (net (code "52") (name "Net-(PCB1-D13{slash}SCK)") (class "Default")
      (node (ref "PCB1") (pin "16") (pinfunction "D13/SCK_16") (pintype "bidirectional"))
      (node (ref "Q1") (pin "1") (pinfunction "G_1") (pintype "passive"))
      (node (ref "R29") (pin "2") (pinfunction "2_2") (pintype "passive"))
      (node (ref "TP15") (pin "1") (pinfunction "1_1") (pintype "passive"))
    )
    (net (code "53") (name "Net-(PCB1-RESET-Pad28)") (class "Default")
      (node (ref "PCB1") (pin "28") (pinfunction "RESET_28") (pintype "input"))
      (node (ref "PCB1") (pin "3") (pinfunction "RESET_3") (pintype "input"))
      (node (ref "TP27") (pin "1") (pinfunction "1_1") (pintype "passive"))
    )
    (net (code "54") (name "Net-(RED1-C)") (class "Default")
      (node (ref "RED1") (pin "CATHODE") (pinfunction "C_CATHODE") (pintype "passive"))
      (node (ref "RED2") (pin "ANODE") (pinfunction "A_ANODE") (pintype "passive"))
    )
    (net (code "55") (name "Net-(RED2-C)") (class "Default")
      (node (ref "RED2") (pin "CATHODE") (pinfunction "C_CATHODE") (pintype "passive"))
      (node (ref "RED3") (pin "ANODE") (pinfunction "A_ANODE") (pintype "passive"))
    )
    (net (code "56") (name "Net-(RED3-C)") (class "Default")
      (node (ref "RED3") (pin "CATHODE") (pinfunction "C_CATHODE") (pintype "passive"))
      (node (ref "RED4") (pin "ANODE") (pinfunction "A_ANODE") (pintype "passive"))
    )
    (net (code "57") (name "Net-(RED4-C)") (class "Default")
      (node (ref "RED4") (pin "CATHODE") (pinfunction "C_CATHODE") (pintype "passive"))
      (node (ref "RED5") (pin "ANODE") (pinfunction "A_ANODE") (pintype "passive"))
    )
    (net (code "58") (name "Net-(RED5-C)") (class "Default")
      (node (ref "RED5") (pin "CATHODE") (pinfunction "C_CATHODE") (pintype "passive"))
      (node (ref "RED6") (pin "ANODE") (pinfunction "A_ANODE") (pintype "passive"))
    )
    (net (code "59") (name "Net-(RED6-C)") (class "Default")
      (node (ref "RED6") (pin "CATHODE") (pinfunction "C_CATHODE") (pintype "passive"))
      (node (ref "RED7") (pin "ANODE") (pinfunction "A_ANODE") (pintype "passive"))
    )
    (net (code "60") (name "Net-(RED7-C)") (class "Default")
      (node (ref "RED7") (pin "CATHODE") (pinfunction "C_CATHODE") (pintype "passive"))
      (node (ref "RED8") (pin "ANODE") (pinfunction "A_ANODE") (pintype "passive"))
    )
    (net (code "61") (name "Net-(RED8-C)") (class "Default")
      (node (ref "RED8") (pin "CATHODE") (pinfunction "C_CATHODE") (pintype "passive"))
      (node (ref "RED9") (pin "ANODE") (pinfunction "A_ANODE") (pintype "passive"))
    )
    (net (code "62") (name "Net-(RED10-A)") (class "Default")
      (node (ref "RED10") (pin "ANODE") (pinfunction "A_ANODE") (pintype "passive"))
      (node (ref "RED9") (pin "CATHODE") (pinfunction "C_CATHODE") (pintype "passive"))
    )
    (net (code "63") (name "Net-(RED10-C)") (class "Default")
      (node (ref "RED10") (pin "CATHODE") (pinfunction "C_CATHODE") (pintype "passive"))
      (node (ref "RED11") (pin "ANODE") (pinfunction "A_ANODE") (pintype "passive"))
    )
    (net (code "64") (name "Net-(RED11-C)") (class "Default")
      (node (ref "RED11") (pin "CATHODE") (pinfunction "C_CATHODE") (pintype "passive"))
      (node (ref "RED12") (pin "ANODE") (pinfunction "A_ANODE") (pintype "passive"))
    )
    (net (code "65") (name "Net-(RED12-C)") (class "Default")
      (node (ref "RED12") (pin "CATHODE") (pinfunction "C_CATHODE") (pintype "passive"))
      (node (ref "RED13") (pin "ANODE") (pinfunction "A_ANODE") (pintype "passive"))
    )
    (net (code "66") (name "Net-(RED13-C)") (class "Default")
      (node (ref "RED13") (pin "CATHODE") (pinfunction "C_CATHODE") (pintype "passive"))
      (node (ref "RED14") (pin "ANODE") (pinfunction "A_ANODE") (pintype "passive"))
    )
    (net (code "67") (name "Net-(RED14-C)") (class "Default")
      (node (ref "RED14") (pin "CATHODE") (pinfunction "C_CATHODE") (pintype "passive"))
      (node (ref "RED15") (pin "ANODE") (pinfunction "A_ANODE") (pintype "passive"))
    )
    (net (code "68") (name "Net-(RED15-C)") (class "Default")
      (node (ref "C8") (pin "2") (pinfunction "2_2") (pintype "passive"))
      (node (ref "R16") (pin "1") (pinfunction "1_1") (pintype "passive"))
      (node (ref "R19") (pin "2") (pinfunction "2_2") (pintype "passive"))
      (node (ref "RED15") (pin "CATHODE") (pinfunction "C_CATHODE") (pintype "passive"))
      (node (ref "TP21") (pin "1") (pinfunction "1_1") (pintype "passive"))
    )
    (net (code "69") (name "Net-(U$10-P$2)") (class "Default")
      (node (ref "Q1") (pin "2") (pinfunction "D_2") (pintype "passive"))
      (node (ref "Q1") (pin "4") (pinfunction "D_4") (pintype "passive"))
      (node (ref "U$10") (pin "G2") (pinfunction "P$2_G2") (pintype "bidirectional"))
      (node (ref "U$7") (pin "G2") (pinfunction "P$2_G2") (pintype "bidirectional"))
      (node (ref "U$8") (pin "G2") (pinfunction "P$2_G2") (pintype "bidirectional"))
      (node (ref "U$9") (pin "G2") (pinfunction "P$2_G2") (pintype "bidirectional"))
    )
    (net (code "70") (name "Net-(U1-BOOT)") (class "Default")
      (node (ref "C3") (pin "1") (pinfunction "1_1") (pintype "passive"))
      (node (ref "U1") (pin "1") (pinfunction "BOOT_1") (pintype "bidirectional"))
    )
    (net (code "71") (name "Net-(U1-COMP)") (class "Default")
      (node (ref "C11") (pin "1") (pinfunction "1_1") (pintype "passive"))
      (node (ref "U1") (pin "8") (pinfunction "COMP_8") (pintype "bidirectional"))
    )
    (net (code "72") (name "Net-(U1-IADJ)") (class "Default")
      (node (ref "R26") (pin "1") (pinfunction "1_1") (pintype "passive"))
      (node (ref "R28") (pin "2") (pinfunction "2_2") (pintype "passive"))
      (node (ref "TP8") (pin "1") (pinfunction "1_1") (pintype "passive"))
      (node (ref "U1") (pin "6") (pinfunction "IADJ_6") (pintype "bidirectional"))
    )
    (net (code "73") (name "Net-(U1-ISENSE)") (class "Default")
      (node (ref "R15") (pin "2") (pinfunction "2_2") (pintype "passive"))
      (node (ref "U1") (pin "7") (pinfunction "ISENSE_7") (pintype "bidirectional"))
    )
    (net (code "74") (name "Net-(U1-PDIM)") (class "Default")
      (node (ref "TP29") (pin "1") (pinfunction "1_1") (pintype "passive"))
      (node (ref "U1") (pin "4") (pinfunction "PDIM_4") (pintype "bidirectional"))
    )
    (net (code "75") (name "Net-(U1-RT{slash}CLK)") (class "Default")
      (node (ref "R22") (pin "2") (pinfunction "2_2") (pintype "passive"))
      (node (ref "U1") (pin "5") (pinfunction "RT/CLK_5") (pintype "bidirectional"))
    )
    (net (code "76") (name "Net-(U1-UVLO)") (class "Default")
      (node (ref "R10") (pin "1") (pinfunction "1_1") (pintype "passive"))
      (node (ref "R9") (pin "2") (pinfunction "2_2") (pintype "passive"))
      (node (ref "TP11") (pin "1") (pinfunction "1_1") (pintype "passive"))
      (node (ref "U1") (pin "3") (pinfunction "UVLO_3") (pintype "bidirectional"))
    )
    (net (code "77") (name "Net-(U2-BOOT)") (class "Default")
      (node (ref "C2") (pin "1") (pinfunction "1_1") (pintype "passive"))
      (node (ref "U2") (pin "1") (pinfunction "BOOT_1") (pintype "bidirectional"))
    )
    (net (code "78") (name "Net-(U2-COMP)") (class "Default")
      (node (ref "C10") (pin "1") (pinfunction "1_1") (pintype "passive"))
      (node (ref "U2") (pin "8") (pinfunction "COMP_8") (pintype "bidirectional"))
    )
    (net (code "79") (name "Net-(U2-IADJ)") (class "Default")
      (node (ref "R25") (pin "1") (pinfunction "1_1") (pintype "passive"))
      (node (ref "R30") (pin "2") (pinfunction "2_2") (pintype "passive"))
      (node (ref "TP7") (pin "1") (pinfunction "1_1") (pintype "passive"))
      (node (ref "U2") (pin "6") (pinfunction "IADJ_6") (pintype "bidirectional"))
    )
    (net (code "80") (name "Net-(U2-ISENSE)") (class "Default")
      (node (ref "R16") (pin "2") (pinfunction "2_2") (pintype "passive"))
      (node (ref "U2") (pin "7") (pinfunction "ISENSE_7") (pintype "bidirectional"))
    )
    (net (code "81") (name "Net-(U2-PDIM)") (class "Default")
      (node (ref "TP28") (pin "1") (pinfunction "1_1") (pintype "passive"))
      (node (ref "U2") (pin "4") (pinfunction "PDIM_4") (pintype "bidirectional"))
    )
    (net (code "82") (name "Net-(U2-RT{slash}CLK)") (class "Default")
      (node (ref "R21") (pin "2") (pinfunction "2_2") (pintype "passive"))
      (node (ref "U2") (pin "5") (pinfunction "RT/CLK_5") (pintype "bidirectional"))
    )
    (net (code "83") (name "Net-(U2-UVLO)") (class "Default")
      (node (ref "R7") (pin "2") (pinfunction "2_2") (pintype "passive"))
      (node (ref "R8") (pin "1") (pinfunction "1_1") (pintype "passive"))
      (node (ref "TP10") (pin "1") (pinfunction "1_1") (pintype "passive"))
      (node (ref "U2") (pin "3") (pinfunction "UVLO_3") (pintype "bidirectional"))
    )
    (net (code "84") (name "Net-(U3-BOOT)") (class "Default")
      (node (ref "C1") (pin "1") (pinfunction "1_1") (pintype "passive"))
      (node (ref "U3") (pin "1") (pinfunction "BOOT_1") (pintype "bidirectional"))
    )
    (net (code "85") (name "Net-(U3-COMP)") (class "Default")
      (node (ref "C12") (pin "1") (pinfunction "1_1") (pintype "passive"))
      (node (ref "U3") (pin "8") (pinfunction "COMP_8") (pintype "bidirectional"))
    )
    (net (code "86") (name "Net-(U3-IADJ)") (class "Default")
      (node (ref "R24") (pin "1") (pinfunction "1_1") (pintype "passive"))
      (node (ref "R31") (pin "2") (pinfunction "2_2") (pintype "passive"))
      (node (ref "TP6") (pin "1") (pinfunction "1_1") (pintype "passive"))
      (node (ref "U3") (pin "6") (pinfunction "IADJ_6") (pintype "bidirectional"))
    )
    (net (code "87") (name "Net-(U3-ISENSE)") (class "Default")
      (node (ref "R17") (pin "2") (pinfunction "2_2") (pintype "passive"))
      (node (ref "U3") (pin "7") (pinfunction "ISENSE_7") (pintype "bidirectional"))
    )
    (net (code "88") (name "Net-(U3-PDIM)") (class "Default")
      (node (ref "TP30") (pin "1") (pinfunction "1_1") (pintype "passive"))
      (node (ref "U3") (pin "4") (pinfunction "PDIM_4") (pintype "bidirectional"))
    )
    (net (code "89") (name "Net-(U3-RT{slash}CLK)") (class "Default")
      (node (ref "R23") (pin "2") (pinfunction "2_2") (pintype "passive"))
      (node (ref "U3") (pin "5") (pinfunction "RT/CLK_5") (pintype "bidirectional"))
    )
    (net (code "90") (name "Net-(U3-UVLO)") (class "Default")
      (node (ref "R5") (pin "2") (pinfunction "2_2") (pintype "passive"))
      (node (ref "R6") (pin "1") (pinfunction "1_1") (pintype "passive"))
      (node (ref "TP9") (pin "1") (pinfunction "1_1") (pintype "passive"))
      (node (ref "U3") (pin "3") (pinfunction "UVLO_3") (pintype "bidirectional"))
    )
    (net (code "91") (name "Net-(U4-VOUTA)") (class "Default")
      (node (ref "R31") (pin "1") (pinfunction "1_1") (pintype "passive"))
      (node (ref "U4") (pin "6") (pinfunction "VOUTA_6") (pintype "bidirectional"))
    )
    (net (code "92") (name "Net-(U4-VOUTB)") (class "Default")
      (node (ref "R30") (pin "1") (pinfunction "1_1") (pintype "passive"))
      (node (ref "U4") (pin "7") (pinfunction "VOUTB_7") (pintype "bidirectional"))
    )
    (net (code "93") (name "Net-(U4-VOUTC)") (class "Default")
      (node (ref "R28") (pin "1") (pinfunction "1_1") (pintype "passive"))
      (node (ref "U4") (pin "8") (pinfunction "VOUTC_8") (pintype "bidirectional"))
    )
    (net (code "94") (name "Net-(U4-VOUTD)") (class "Default")
      (node (ref "TP16") (pin "1") (pinfunction "1_1") (pintype "passive"))
      (node (ref "U4") (pin "9") (pinfunction "VOUTD_9") (pintype "bidirectional"))
    )
    (net (code "95") (name "unconnected-(J1-2-PadP$3)") (class "Default")
      (node (ref "J1") (pin "P$3") (pinfunction "2_P$3") (pintype "passive"))
    )
    (net (code "96") (name "unconnected-(J2-2-PadP$3)") (class "Default")
      (node (ref "J2") (pin "P$3") (pinfunction "2_P$3") (pintype "passive"))
    )
    (net (code "97") (name "unconnected-(PCB1-A6-Pad25)") (class "Default")
      (node (ref "PCB1") (pin "25") (pinfunction "A6_25") (pintype "input"))
    )
    (net (code "98") (name "unconnected-(PCB1-A7-Pad26)") (class "Default")
      (node (ref "PCB1") (pin "26") (pinfunction "A7_26") (pintype "input"))
    )
    (net (code "99") (name "unconnected-(PCB1-D0{slash}RX-Pad2)") (class "Default")
      (node (ref "PCB1") (pin "2") (pinfunction "D0/RX_2") (pintype "bidirectional"))
    )
    (net (code "100") (name "unconnected-(PCB1-D1{slash}TX-Pad1)") (class "Default")
      (node (ref "PCB1") (pin "1") (pinfunction "D1/TX_1") (pintype "bidirectional"))
    )
    (net (code "101") (name "unconnected-(PCB1-D2-Pad5)") (class "Default")
      (node (ref "PCB1") (pin "5") (pinfunction "D2_5") (pintype "bidirectional"))
    )
    (net (code "102") (name "unconnected-(PCB1-D3-Pad6)") (class "Default")
      (node (ref "PCB1") (pin "6") (pinfunction "D3_6") (pintype "bidirectional"))
    )
    (net (code "103") (name "unconnected-(PCB1-D4-Pad7)") (class "Default")
      (node (ref "PCB1") (pin "7") (pinfunction "D4_7") (pintype "bidirectional"))
    )
    (net (code "104") (name "unconnected-(PCB1-D5-Pad8)") (class "Default")
      (node (ref "PCB1") (pin "8") (pinfunction "D5_8") (pintype "bidirectional"))
    )
    (net (code "105") (name "unconnected-(PCB1-D6-Pad9)") (class "Default")
      (node (ref "PCB1") (pin "9") (pinfunction "D6_9") (pintype "bidirectional"))
    )
    (net (code "106") (name "unconnected-(PCB1-D7-Pad10)") (class "Default")
      (node (ref "PCB1") (pin "10") (pinfunction "D7_10") (pintype "bidirectional"))
    )
    (net (code "107") (name "unconnected-(PCB1-D8-Pad11)") (class "Default")
      (node (ref "PCB1") (pin "11") (pinfunction "D8_11") (pintype "bidirectional"))
    )
    (net (code "108") (name "unconnected-(PCB1-D9-Pad12)") (class "Default")
      (node (ref "PCB1") (pin "12") (pinfunction "D9_12") (pintype "bidirectional"))
    )
    (net (code "109") (name "unconnected-(PCB1-D10-Pad13)") (class "Default")
      (node (ref "PCB1") (pin "13") (pinfunction "D10_13") (pintype "bidirectional"))
    )
  )
)
